# LED_Point_Gate_Drive.net
KiCad netlist of a schematic drawn in Altium Designer
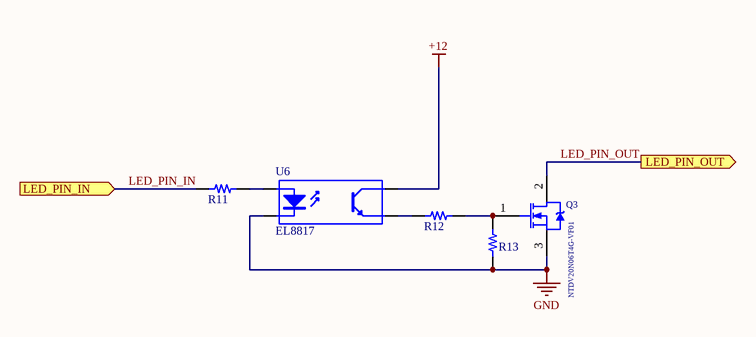
[diagram p0: LED_Point_Gate Drive.SchDoc]

(export (version "E")
  (design (tool "Eeschema 10.0.6"))
  (components
    (comp (ref "Q3")
      (value "NTDV20N06T4G-VF01")
      (footprint "DPAK228P991X238-3N")
      (description "MOSFET N-CH 60V 20A DPAK")
      (fields
        (field (name "MANUFACTURE PART NUMBER") "IRF540N_R4942")
        (field (name "PUBLISHER") "Altium Limited")
      )
      (libsource (lib "HYD_EMER_2") (part "IRF540NS"))
    )
    (comp (ref "R11")
      (value "1K")
      (footprint "RES SMD 0805")
      (description "RES SMD 1K OHM 1% 1/4W 0805")
      (libsource (lib "DIY-USB Led Controller") (part "RESISTOR"))
    )
    (comp (ref "R12")
      (value "48R")
      (footprint "RES SMD 0805")
      (description "RES SMD 48 OHM 1% 1/4W 0805")
      (libsource (lib "DIY-USB Led Controller") (part "RESISTOR"))
    )
    (comp (ref "R13")
      (value "10K")
      (footprint "RES SMD 0805")
      (description "RES SMD 10K OHM 1% 1/4W 0805")
      (libsource (lib "DIY-USB Led Controller") (part "RESISTOR"))
    )
    (comp (ref "U6")
      (value "EL8817")
      (footprint "DIP-4 GULLWING")
      (description "Optoisolator Transistor Output 5000Vrms 1 Channel 4-SMD")
      (libsource (lib "REMOTE RGBW CONTROLLER") (part "PC817"))
    )
  )
  (nets
    (net (code "1") (name "+12") (class "Default")
      (node (ref "U6") (pin "4") (pinfunction "C_4") (pintype "passive"))
    )
    (net (code "2") (name "/LED_PIN_IN") (class "Default")
      (node (ref "R11") (pin "1") (pinfunction "1_1") (pintype "passive"))
    )
    (net (code "3") (name "/LED_PIN_OUT") (class "Default")
      (node (ref "Q3") (pin "2") (pinfunction "D_2") (pintype "passive"))
    )
    (net (code "4") (name "GND") (class "Default")
      (node (ref "Q3") (pin "3") (pinfunction "S_3") (pintype "passive"))
      (node (ref "R13") (pin "1") (pinfunction "1_1") (pintype "passive"))
      (node (ref "U6") (pin "2") (pinfunction "K_2") (pintype "passive"))
    )
    (net (code "5") (name "Net-(Q3-G)") (class "Default")
      (node (ref "Q3") (pin "1") (pinfunction "G_1") (pintype "passive"))
      (node (ref "R12") (pin "2") (pinfunction "2_2") (pintype "passive"))
      (node (ref "R13") (pin "2") (pinfunction "2_2") (pintype "passive"))
    )
    (net (code "6") (name "Net-(U6-A)") (class "Default")
      (node (ref "R11") (pin "2") (pinfunction "2_2") (pintype "passive"))
      (node (ref "U6") (pin "1") (pinfunction "A_1") (pintype "passive"))
    )
    (net (code "7") (name "Net-(U6-E)") (class "Default")
      (node (ref "R12") (pin "1") (pinfunction "1_1") (pintype "passive"))
      (node (ref "U6") (pin "3") (pinfunction "E_3") (pintype "passive"))
    )
  )
)
